# LEDARRAYHI.net
KiCad netlist of a schematic drawn in EAGLE
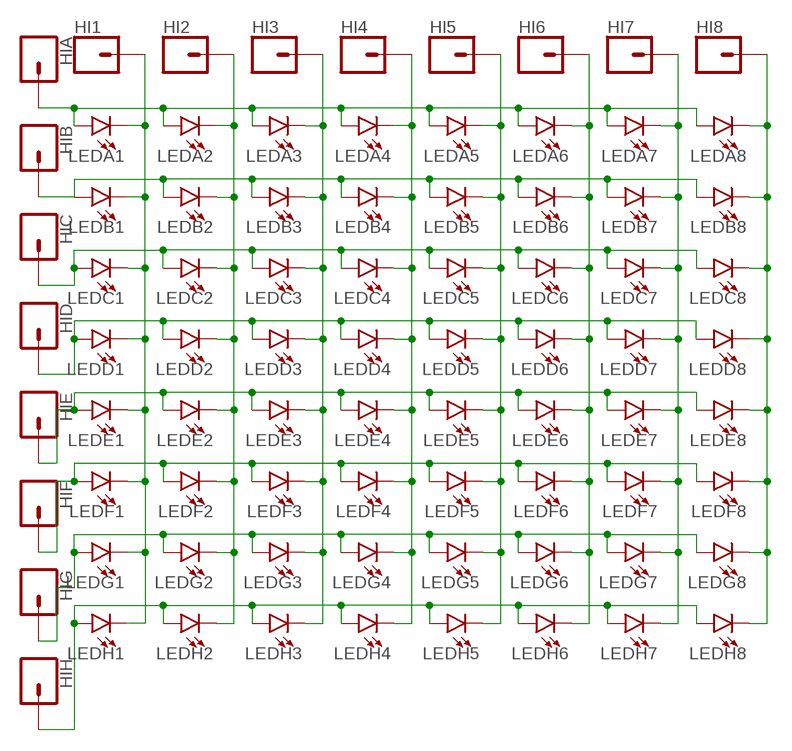
[diagram p0: schematic, sheet 1]

(export (version "E")
  (design (tool "Eeschema 10.0.6"))
  (components
    (comp (ref "HI1")
      (value "CONN_01PTH_NO_SILK_KIT")
      (footprint "eagle-import:1X01NS_KIT")
      (libsource (lib "eagle-import") (part "CONN_01PTH_NO_SILK_KIT"))
    )
    (comp (ref "HI2")
      (value "CONN_01PTH_NO_SILK_KIT")
      (footprint "eagle-import:1X01NS_KIT")
      (libsource (lib "eagle-import") (part "CONN_01PTH_NO_SILK_KIT"))
    )
    (comp (ref "HI3")
      (value "CONN_01PTH_NO_SILK_KIT")
      (footprint "eagle-import:1X01NS_KIT")
      (libsource (lib "eagle-import") (part "CONN_01PTH_NO_SILK_KIT"))
    )
    (comp (ref "HI4")
      (value "CONN_01PTH_NO_SILK_KIT")
      (footprint "eagle-import:1X01NS_KIT")
      (libsource (lib "eagle-import") (part "CONN_01PTH_NO_SILK_KIT"))
    )
    (comp (ref "HI5")
      (value "CONN_01PTH_NO_SILK_KIT")
      (footprint "eagle-import:1X01NS_KIT")
      (libsource (lib "eagle-import") (part "CONN_01PTH_NO_SILK_KIT"))
    )
    (comp (ref "HI6")
      (value "CONN_01PTH_NO_SILK_KIT")
      (footprint "eagle-import:1X01NS_KIT")
      (libsource (lib "eagle-import") (part "CONN_01PTH_NO_SILK_KIT"))
    )
    (comp (ref "HI7")
      (value "CONN_01PTH_NO_SILK_KIT")
      (footprint "eagle-import:1X01NS_KIT")
      (libsource (lib "eagle-import") (part "CONN_01PTH_NO_SILK_KIT"))
    )
    (comp (ref "HI8")
      (value "CONN_01PTH_NO_SILK_KIT")
      (footprint "eagle-import:1X01NS_KIT")
      (libsource (lib "eagle-import") (part "CONN_01PTH_NO_SILK_KIT"))
    )
    (comp (ref "HIA")
      (value "CONN_01PTH_NO_SILK_KIT")
      (footprint "eagle-import:1X01NS_KIT")
      (libsource (lib "eagle-import") (part "CONN_01PTH_NO_SILK_KIT"))
    )
    (comp (ref "HIB")
      (value "CONN_01PTH_NO_SILK_KIT")
      (footprint "eagle-import:1X01NS_KIT")
      (libsource (lib "eagle-import") (part "CONN_01PTH_NO_SILK_KIT"))
    )
    (comp (ref "HIC")
      (value "CONN_01PTH_NO_SILK_KIT")
      (footprint "eagle-import:1X01NS_KIT")
      (libsource (lib "eagle-import") (part "CONN_01PTH_NO_SILK_KIT"))
    )
    (comp (ref "HID")
      (value "CONN_01PTH_NO_SILK_KIT")
      (footprint "eagle-import:1X01NS_KIT")
      (libsource (lib "eagle-import") (part "CONN_01PTH_NO_SILK_KIT"))
    )
    (comp (ref "HIE")
      (value "CONN_01PTH_NO_SILK_KIT")
      (footprint "eagle-import:1X01NS_KIT")
      (libsource (lib "eagle-import") (part "CONN_01PTH_NO_SILK_KIT"))
    )
    (comp (ref "HIF")
      (value "CONN_01PTH_NO_SILK_KIT")
      (footprint "eagle-import:1X01NS_KIT")
      (libsource (lib "eagle-import") (part "CONN_01PTH_NO_SILK_KIT"))
    )
    (comp (ref "HIG")
      (value "CONN_01PTH_NO_SILK_KIT")
      (footprint "eagle-import:1X01NS_KIT")
      (libsource (lib "eagle-import") (part "CONN_01PTH_NO_SILK_KIT"))
    )
    (comp (ref "HIH")
      (value "CONN_01PTH_NO_SILK_KIT")
      (footprint "eagle-import:1X01NS_KIT")
      (libsource (lib "eagle-import") (part "CONN_01PTH_NO_SILK_KIT"))
    )
    (comp (ref "LEDA1")
      (value "LED3MM")
      (footprint "eagle-import:LED_3MM")
      (libsource (lib "eagle-import") (part "LED3MM"))
    )
    (comp (ref "LEDA2")
      (value "LED3MM")
      (footprint "eagle-import:LED_3MM")
      (libsource (lib "eagle-import") (part "LED3MM"))
    )
    (comp (ref "LEDA3")
      (value "LED3MM")
      (footprint "eagle-import:LED_3MM")
      (libsource (lib "eagle-import") (part "LED3MM"))
    )
    (comp (ref "LEDA4")
      (value "LED3MM")
      (footprint "eagle-import:LED_3MM")
      (libsource (lib "eagle-import") (part "LED3MM"))
    )
    (comp (ref "LEDA5")
      (value "LED3MM")
      (footprint "eagle-import:LED_3MM")
      (libsource (lib "eagle-import") (part "LED3MM"))
    )
    (comp (ref "LEDA6")
      (value "LED3MM")
      (footprint "eagle-import:LED_3MM")
      (libsource (lib "eagle-import") (part "LED3MM"))
    )
    (comp (ref "LEDA7")
      (value "LED3MM")
      (footprint "eagle-import:LED_3MM")
      (libsource (lib "eagle-import") (part "LED3MM"))
    )
    (comp (ref "LEDA8")
      (value "LED3MM")
      (footprint "eagle-import:LED_3MM")
      (libsource (lib "eagle-import") (part "LED3MM"))
    )
    (comp (ref "LEDB1")
      (value "LED3MM")
      (footprint "eagle-import:LED_3MM")
      (libsource (lib "eagle-import") (part "LED3MM"))
    )
    (comp (ref "LEDB2")
      (value "LED3MM")
      (footprint "eagle-import:LED_3MM")
      (libsource (lib "eagle-import") (part "LED3MM"))
    )
    (comp (ref "LEDB3")
      (value "LED3MM")
      (footprint "eagle-import:LED_3MM")
      (libsource (lib "eagle-import") (part "LED3MM"))
    )
    (comp (ref "LEDB4")
      (value "LED3MM")
      (footprint "eagle-import:LED_3MM")
      (libsource (lib "eagle-import") (part "LED3MM"))
    )
    (comp (ref "LEDB5")
      (value "LED3MM")
      (footprint "eagle-import:LED_3MM")
      (libsource (lib "eagle-import") (part "LED3MM"))
    )
    (comp (ref "LEDB6")
      (value "LED3MM")
      (footprint "eagle-import:LED_3MM")
      (libsource (lib "eagle-import") (part "LED3MM"))
    )
    (comp (ref "LEDB7")
      (value "LED3MM")
      (footprint "eagle-import:LED_3MM")
      (libsource (lib "eagle-import") (part "LED3MM"))
    )
    (comp (ref "LEDB8")
      (value "LED3MM")
      (footprint "eagle-import:LED_3MM")
      (libsource (lib "eagle-import") (part "LED3MM"))
    )
    (comp (ref "LEDC1")
      (value "LED3MM")
      (footprint "eagle-import:LED_3MM")
      (libsource (lib "eagle-import") (part "LED3MM"))
    )
    (comp (ref "LEDC2")
      (value "LED3MM")
      (footprint "eagle-import:LED_3MM")
      (libsource (lib "eagle-import") (part "LED3MM"))
    )
    (comp (ref "LEDC3")
      (value "LED3MM")
      (footprint "eagle-import:LED_3MM")
      (libsource (lib "eagle-import") (part "LED3MM"))
    )
    (comp (ref "LEDC4")
      (value "LED3MM")
      (footprint "eagle-import:LED_3MM")
      (libsource (lib "eagle-import") (part "LED3MM"))
    )
    (comp (ref "LEDC5")
      (value "LED3MM")
      (footprint "eagle-import:LED_3MM")
      (libsource (lib "eagle-import") (part "LED3MM"))
    )
    (comp (ref "LEDC6")
      (value "LED3MM")
      (footprint "eagle-import:LED_3MM")
      (libsource (lib "eagle-import") (part "LED3MM"))
    )
    (comp (ref "LEDC7")
      (value "LED3MM")
      (footprint "eagle-import:LED_3MM")
      (libsource (lib "eagle-import") (part "LED3MM"))
    )
    (comp (ref "LEDC8")
      (value "LED3MM")
      (footprint "eagle-import:LED_3MM")
      (libsource (lib "eagle-import") (part "LED3MM"))
    )
    (comp (ref "LEDD1")
      (value "LED3MM")
      (footprint "eagle-import:LED_3MM")
      (libsource (lib "eagle-import") (part "LED3MM"))
    )
    (comp (ref "LEDD2")
      (value "LED3MM")
      (footprint "eagle-import:LED_3MM")
      (libsource (lib "eagle-import") (part "LED3MM"))
    )
    (comp (ref "LEDD3")
      (value "LED3MM")
      (footprint "eagle-import:LED_3MM")
      (libsource (lib "eagle-import") (part "LED3MM"))
    )
    (comp (ref "LEDD4")
      (value "LED3MM")
      (footprint "eagle-import:LED_3MM")
      (libsource (lib "eagle-import") (part "LED3MM"))
    )
    (comp (ref "LEDD5")
      (value "LED3MM")
      (footprint "eagle-import:LED_3MM")
      (libsource (lib "eagle-import") (part "LED3MM"))
    )
    (comp (ref "LEDD6")
      (value "LED3MM")
      (footprint "eagle-import:LED_3MM")
      (libsource (lib "eagle-import") (part "LED3MM"))
    )
    (comp (ref "LEDD7")
      (value "LED3MM")
      (footprint "eagle-import:LED_3MM")
      (libsource (lib "eagle-import") (part "LED3MM"))
    )
    (comp (ref "LEDD8")
      (value "LED3MM")
      (footprint "eagle-import:LED_3MM")
      (libsource (lib "eagle-import") (part "LED3MM"))
    )
    (comp (ref "LEDE1")
      (value "LED3MM")
      (footprint "eagle-import:LED_3MM")
      (libsource (lib "eagle-import") (part "LED3MM"))
    )
    (comp (ref "LEDE2")
      (value "LED3MM")
      (footprint "eagle-import:LED_3MM")
      (libsource (lib "eagle-import") (part "LED3MM"))
    )
    (comp (ref "LEDE3")
      (value "LED3MM")
      (footprint "eagle-import:LED_3MM")
      (libsource (lib "eagle-import") (part "LED3MM"))
    )
    (comp (ref "LEDE4")
      (value "LED3MM")
      (footprint "eagle-import:LED_3MM")
      (libsource (lib "eagle-import") (part "LED3MM"))
    )
    (comp (ref "LEDE5")
      (value "LED3MM")
      (footprint "eagle-import:LED_3MM")
      (libsource (lib "eagle-import") (part "LED3MM"))
    )
    (comp (ref "LEDE6")
      (value "LED3MM")
      (footprint "eagle-import:LED_3MM")
      (libsource (lib "eagle-import") (part "LED3MM"))
    )
    (comp (ref "LEDE7")
      (value "LED3MM")
      (footprint "eagle-import:LED_3MM")
      (libsource (lib "eagle-import") (part "LED3MM"))
    )
    (comp (ref "LEDE8")
      (value "LED3MM")
      (footprint "eagle-import:LED_3MM")
      (libsource (lib "eagle-import") (part "LED3MM"))
    )
    (comp (ref "LEDF1")
      (value "LED3MM")
      (footprint "eagle-import:LED_3MM")
      (libsource (lib "eagle-import") (part "LED3MM"))
    )
    (comp (ref "LEDF2")
      (value "LED3MM")
      (footprint "eagle-import:LED_3MM")
      (libsource (lib "eagle-import") (part "LED3MM"))
    )
    (comp (ref "LEDF3")
      (value "LED3MM")
      (footprint "eagle-import:LED_3MM")
      (libsource (lib "eagle-import") (part "LED3MM"))
    )
    (comp (ref "LEDF4")
      (value "LED3MM")
      (footprint "eagle-import:LED_3MM")
      (libsource (lib "eagle-import") (part "LED3MM"))
    )
    (comp (ref "LEDF5")
      (value "LED3MM")
      (footprint "eagle-import:LED_3MM")
      (libsource (lib "eagle-import") (part "LED3MM"))
    )
    (comp (ref "LEDF6")
      (value "LED3MM")
      (footprint "eagle-import:LED_3MM")
      (libsource (lib "eagle-import") (part "LED3MM"))
    )
    (comp (ref "LEDF7")
      (value "LED3MM")
      (footprint "eagle-import:LED_3MM")
      (libsource (lib "eagle-import") (part "LED3MM"))
    )
    (comp (ref "LEDF8")
      (value "LED3MM")
      (footprint "eagle-import:LED_3MM")
      (libsource (lib "eagle-import") (part "LED3MM"))
    )
    (comp (ref "LEDG1")
      (value "LED3MM")
      (footprint "eagle-import:LED_3MM")
      (libsource (lib "eagle-import") (part "LED3MM"))
    )
    (comp (ref "LEDG2")
      (value "LED3MM")
      (footprint "eagle-import:LED_3MM")
      (libsource (lib "eagle-import") (part "LED3MM"))
    )
    (comp (ref "LEDG3")
      (value "LED3MM")
      (footprint "eagle-import:LED_3MM")
      (libsource (lib "eagle-import") (part "LED3MM"))
    )
    (comp (ref "LEDG4")
      (value "LED3MM")
      (footprint "eagle-import:LED_3MM")
      (libsource (lib "eagle-import") (part "LED3MM"))
    )
    (comp (ref "LEDG5")
      (value "LED3MM")
      (footprint "eagle-import:LED_3MM")
      (libsource (lib "eagle-import") (part "LED3MM"))
    )
    (comp (ref "LEDG6")
      (value "LED3MM")
      (footprint "eagle-import:LED_3MM")
      (libsource (lib "eagle-import") (part "LED3MM"))
    )
    (comp (ref "LEDG7")
      (value "LED3MM")
      (footprint "eagle-import:LED_3MM")
      (libsource (lib "eagle-import") (part "LED3MM"))
    )
    (comp (ref "LEDG8")
      (value "LED3MM")
      (footprint "eagle-import:LED_3MM")
      (libsource (lib "eagle-import") (part "LED3MM"))
    )
    (comp (ref "LEDH1")
      (value "LED3MM")
      (footprint "eagle-import:LED_3MM")
      (libsource (lib "eagle-import") (part "LED3MM"))
    )
    (comp (ref "LEDH2")
      (value "LED3MM")
      (footprint "eagle-import:LED_3MM")
      (libsource (lib "eagle-import") (part "LED3MM"))
    )
    (comp (ref "LEDH3")
      (value "LED3MM")
      (footprint "eagle-import:LED_3MM")
      (libsource (lib "eagle-import") (part "LED3MM"))
    )
    (comp (ref "LEDH4")
      (value "LED3MM")
      (footprint "eagle-import:LED_3MM")
      (libsource (lib "eagle-import") (part "LED3MM"))
    )
    (comp (ref "LEDH5")
      (value "LED3MM")
      (footprint "eagle-import:LED_3MM")
      (libsource (lib "eagle-import") (part "LED3MM"))
    )
    (comp (ref "LEDH6")
      (value "LED3MM")
      (footprint "eagle-import:LED_3MM")
      (libsource (lib "eagle-import") (part "LED3MM"))
    )
    (comp (ref "LEDH7")
      (value "LED3MM")
      (footprint "eagle-import:LED_3MM")
      (libsource (lib "eagle-import") (part "LED3MM"))
    )
    (comp (ref "LEDH8")
      (value "LED3MM")
      (footprint "eagle-import:LED_3MM")
      (libsource (lib "eagle-import") (part "LED3MM"))
    )
  )
  (nets
    (net (code "1") (name "Net-(HIA-Pad1)") (class "Default")
      (node (ref "HIA") (pin "1") (pinfunction "1_1") (pintype "passive"))
      (node (ref "LEDA1") (pin "A") (pinfunction "A_A") (pintype "passive"))
      (node (ref "LEDA2") (pin "A") (pinfunction "A_A") (pintype "passive"))
      (node (ref "LEDA3") (pin "A") (pinfunction "A_A") (pintype "passive"))
      (node (ref "LEDA4") (pin "A") (pinfunction "A_A") (pintype "passive"))
      (node (ref "LEDA5") (pin "A") (pinfunction "A_A") (pintype "passive"))
      (node (ref "LEDA6") (pin "A") (pinfunction "A_A") (pintype "passive"))
      (node (ref "LEDA7") (pin "A") (pinfunction "A_A") (pintype "passive"))
      (node (ref "LEDA8") (pin "A") (pinfunction "A_A") (pintype "passive"))
    )
    (net (code "2") (name "Net-(HIB-Pad1)") (class "Default")
      (node (ref "HIB") (pin "1") (pinfunction "1_1") (pintype "passive"))
      (node (ref "LEDB1") (pin "A") (pinfunction "A_A") (pintype "passive"))
      (node (ref "LEDB2") (pin "A") (pinfunction "A_A") (pintype "passive"))
      (node (ref "LEDB3") (pin "A") (pinfunction "A_A") (pintype "passive"))
      (node (ref "LEDB4") (pin "A") (pinfunction "A_A") (pintype "passive"))
      (node (ref "LEDB5") (pin "A") (pinfunction "A_A") (pintype "passive"))
      (node (ref "LEDB6") (pin "A") (pinfunction "A_A") (pintype "passive"))
      (node (ref "LEDB7") (pin "A") (pinfunction "A_A") (pintype "passive"))
      (node (ref "LEDB8") (pin "A") (pinfunction "A_A") (pintype "passive"))
    )
    (net (code "3") (name "Net-(HIC-Pad1)") (class "Default")
      (node (ref "HIC") (pin "1") (pinfunction "1_1") (pintype "passive"))
      (node (ref "LEDC1") (pin "A") (pinfunction "A_A") (pintype "passive"))
      (node (ref "LEDC2") (pin "A") (pinfunction "A_A") (pintype "passive"))
      (node (ref "LEDC3") (pin "A") (pinfunction "A_A") (pintype "passive"))
      (node (ref "LEDC4") (pin "A") (pinfunction "A_A") (pintype "passive"))
      (node (ref "LEDC5") (pin "A") (pinfunction "A_A") (pintype "passive"))
      (node (ref "LEDC6") (pin "A") (pinfunction "A_A") (pintype "passive"))
      (node (ref "LEDC7") (pin "A") (pinfunction "A_A") (pintype "passive"))
      (node (ref "LEDC8") (pin "A") (pinfunction "A_A") (pintype "passive"))
    )
    (net (code "4") (name "Net-(HID-Pad1)") (class "Default")
      (node (ref "HID") (pin "1") (pinfunction "1_1") (pintype "passive"))
      (node (ref "LEDD1") (pin "A") (pinfunction "A_A") (pintype "passive"))
      (node (ref "LEDD2") (pin "A") (pinfunction "A_A") (pintype "passive"))
      (node (ref "LEDD3") (pin "A") (pinfunction "A_A") (pintype "passive"))
      (node (ref "LEDD4") (pin "A") (pinfunction "A_A") (pintype "passive"))
      (node (ref "LEDD5") (pin "A") (pinfunction "A_A") (pintype "passive"))
      (node (ref "LEDD6") (pin "A") (pinfunction "A_A") (pintype "passive"))
      (node (ref "LEDD7") (pin "A") (pinfunction "A_A") (pintype "passive"))
      (node (ref "LEDD8") (pin "A") (pinfunction "A_A") (pintype "passive"))
    )
    (net (code "5") (name "Net-(HIE-Pad1)") (class "Default")
      (node (ref "HIE") (pin "1") (pinfunction "1_1") (pintype "passive"))
      (node (ref "LEDE1") (pin "A") (pinfunction "A_A") (pintype "passive"))
      (node (ref "LEDE2") (pin "A") (pinfunction "A_A") (pintype "passive"))
      (node (ref "LEDE3") (pin "A") (pinfunction "A_A") (pintype "passive"))
      (node (ref "LEDE4") (pin "A") (pinfunction "A_A") (pintype "passive"))
      (node (ref "LEDE5") (pin "A") (pinfunction "A_A") (pintype "passive"))
      (node (ref "LEDE6") (pin "A") (pinfunction "A_A") (pintype "passive"))
      (node (ref "LEDE7") (pin "A") (pinfunction "A_A") (pintype "passive"))
      (node (ref "LEDE8") (pin "A") (pinfunction "A_A") (pintype "passive"))
    )
    (net (code "6") (name "Net-(HIF-Pad1)") (class "Default")
      (node (ref "HIF") (pin "1") (pinfunction "1_1") (pintype "passive"))
      (node (ref "LEDF1") (pin "A") (pinfunction "A_A") (pintype "passive"))
      (node (ref "LEDF2") (pin "A") (pinfunction "A_A") (pintype "passive"))
      (node (ref "LEDF3") (pin "A") (pinfunction "A_A") (pintype "passive"))
      (node (ref "LEDF4") (pin "A") (pinfunction "A_A") (pintype "passive"))
      (node (ref "LEDF5") (pin "A") (pinfunction "A_A") (pintype "passive"))
      (node (ref "LEDF6") (pin "A") (pinfunction "A_A") (pintype "passive"))
      (node (ref "LEDF7") (pin "A") (pinfunction "A_A") (pintype "passive"))
      (node (ref "LEDF8") (pin "A") (pinfunction "A_A") (pintype "passive"))
    )
    (net (code "7") (name "Net-(HIG-Pad1)") (class "Default")
      (node (ref "HIG") (pin "1") (pinfunction "1_1") (pintype "passive"))
      (node (ref "LEDG1") (pin "A") (pinfunction "A_A") (pintype "passive"))
      (node (ref "LEDG2") (pin "A") (pinfunction "A_A") (pintype "passive"))
      (node (ref "LEDG3") (pin "A") (pinfunction "A_A") (pintype "passive"))
      (node (ref "LEDG4") (pin "A") (pinfunction "A_A") (pintype "passive"))
      (node (ref "LEDG5") (pin "A") (pinfunction "A_A") (pintype "passive"))
      (node (ref "LEDG6") (pin "A") (pinfunction "A_A") (pintype "passive"))
      (node (ref "LEDG7") (pin "A") (pinfunction "A_A") (pintype "passive"))
      (node (ref "LEDG8") (pin "A") (pinfunction "A_A") (pintype "passive"))
    )
    (net (code "8") (name "Net-(HIH-Pad1)") (class "Default")
      (node (ref "HIH") (pin "1") (pinfunction "1_1") (pintype "passive"))
      (node (ref "LEDH1") (pin "A") (pinfunction "A_A") (pintype "passive"))
      (node (ref "LEDH2") (pin "A") (pinfunction "A_A") (pintype "passive"))
      (node (ref "LEDH3") (pin "A") (pinfunction "A_A") (pintype "passive"))
      (node (ref "LEDH4") (pin "A") (pinfunction "A_A") (pintype "passive"))
      (node (ref "LEDH5") (pin "A") (pinfunction "A_A") (pintype "passive"))
      (node (ref "LEDH6") (pin "A") (pinfunction "A_A") (pintype "passive"))
      (node (ref "LEDH7") (pin "A") (pinfunction "A_A") (pintype "passive"))
      (node (ref "LEDH8") (pin "A") (pinfunction "A_A") (pintype "passive"))
    )
    (net (code "9") (name "Net-(LEDA1-C)") (class "Default")
      (node (ref "HI1") (pin "1") (pinfunction "1_1") (pintype "passive"))
      (node (ref "LEDA1") (pin "K") (pinfunction "C_K") (pintype "passive"))
      (node (ref "LEDB1") (pin "K") (pinfunction "C_K") (pintype "passive"))
      (node (ref "LEDC1") (pin "K") (pinfunction "C_K") (pintype "passive"))
      (node (ref "LEDD1") (pin "K") (pinfunction "C_K") (pintype "passive"))
      (node (ref "LEDE1") (pin "K") (pinfunction "C_K") (pintype "passive"))
      (node (ref "LEDF1") (pin "K") (pinfunction "C_K") (pintype "passive"))
      (node (ref "LEDG1") (pin "K") (pinfunction "C_K") (pintype "passive"))
      (node (ref "LEDH1") (pin "K") (pinfunction "C_K") (pintype "passive"))
    )
    (net (code "10") (name "Net-(LEDA2-C)") (class "Default")
      (node (ref "HI2") (pin "1") (pinfunction "1_1") (pintype "passive"))
      (node (ref "LEDA2") (pin "K") (pinfunction "C_K") (pintype "passive"))
      (node (ref "LEDB2") (pin "K") (pinfunction "C_K") (pintype "passive"))
      (node (ref "LEDC2") (pin "K") (pinfunction "C_K") (pintype "passive"))
      (node (ref "LEDD2") (pin "K") (pinfunction "C_K") (pintype "passive"))
      (node (ref "LEDE2") (pin "K") (pinfunction "C_K") (pintype "passive"))
      (node (ref "LEDF2") (pin "K") (pinfunction "C_K") (pintype "passive"))
      (node (ref "LEDG2") (pin "K") (pinfunction "C_K") (pintype "passive"))
      (node (ref "LEDH2") (pin "K") (pinfunction "C_K") (pintype "passive"))
    )
    (net (code "11") (name "Net-(LEDA3-C)") (class "Default")
      (node (ref "HI3") (pin "1") (pinfunction "1_1") (pintype "passive"))
      (node (ref "LEDA3") (pin "K") (pinfunction "C_K") (pintype "passive"))
      (node (ref "LEDB3") (pin "K") (pinfunction "C_K") (pintype "passive"))
      (node (ref "LEDC3") (pin "K") (pinfunction "C_K") (pintype "passive"))
      (node (ref "LEDD3") (pin "K") (pinfunction "C_K") (pintype "passive"))
      (node (ref "LEDE3") (pin "K") (pinfunction "C_K") (pintype "passive"))
      (node (ref "LEDF3") (pin "K") (pinfunction "C_K") (pintype "passive"))
      (node (ref "LEDG3") (pin "K") (pinfunction "C_K") (pintype "passive"))
      (node (ref "LEDH3") (pin "K") (pinfunction "C_K") (pintype "passive"))
    )
    (net (code "12") (name "Net-(LEDA4-C)") (class "Default")
      (node (ref "HI4") (pin "1") (pinfunction "1_1") (pintype "passive"))
      (node (ref "LEDA4") (pin "K") (pinfunction "C_K") (pintype "passive"))
      (node (ref "LEDB4") (pin "K") (pinfunction "C_K") (pintype "passive"))
      (node (ref "LEDC4") (pin "K") (pinfunction "C_K") (pintype "passive"))
      (node (ref "LEDD4") (pin "K") (pinfunction "C_K") (pintype "passive"))
      (node (ref "LEDE4") (pin "K") (pinfunction "C_K") (pintype "passive"))
      (node (ref "LEDF4") (pin "K") (pinfunction "C_K") (pintype "passive"))
      (node (ref "LEDG4") (pin "K") (pinfunction "C_K") (pintype "passive"))
      (node (ref "LEDH4") (pin "K") (pinfunction "C_K") (pintype "passive"))
    )
    (net (code "13") (name "Net-(LEDA5-C)") (class "Default")
      (node (ref "HI5") (pin "1") (pinfunction "1_1") (pintype "passive"))
      (node (ref "LEDA5") (pin "K") (pinfunction "C_K") (pintype "passive"))
      (node (ref "LEDB5") (pin "K") (pinfunction "C_K") (pintype "passive"))
      (node (ref "LEDC5") (pin "K") (pinfunction "C_K") (pintype "passive"))
      (node (ref "LEDD5") (pin "K") (pinfunction "C_K") (pintype "passive"))
      (node (ref "LEDE5") (pin "K") (pinfunction "C_K") (pintype "passive"))
      (node (ref "LEDF5") (pin "K") (pinfunction "C_K") (pintype "passive"))
      (node (ref "LEDG5") (pin "K") (pinfunction "C_K") (pintype "passive"))
      (node (ref "LEDH5") (pin "K") (pinfunction "C_K") (pintype "passive"))
    )
    (net (code "14") (name "Net-(LEDA6-C)") (class "Default")
      (node (ref "HI6") (pin "1") (pinfunction "1_1") (pintype "passive"))
      (node (ref "LEDA6") (pin "K") (pinfunction "C_K") (pintype "passive"))
      (node (ref "LEDB6") (pin "K") (pinfunction "C_K") (pintype "passive"))
      (node (ref "LEDC6") (pin "K") (pinfunction "C_K") (pintype "passive"))
      (node (ref "LEDD6") (pin "K") (pinfunction "C_K") (pintype "passive"))
      (node (ref "LEDE6") (pin "K") (pinfunction "C_K") (pintype "passive"))
      (node (ref "LEDF6") (pin "K") (pinfunction "C_K") (pintype "passive"))
      (node (ref "LEDG6") (pin "K") (pinfunction "C_K") (pintype "passive"))
      (node (ref "LEDH6") (pin "K") (pinfunction "C_K") (pintype "passive"))
    )
    (net (code "15") (name "Net-(LEDA7-C)") (class "Default")
      (node (ref "HI7") (pin "1") (pinfunction "1_1") (pintype "passive"))
      (node (ref "LEDA7") (pin "K") (pinfunction "C_K") (pintype "passive"))
      (node (ref "LEDB7") (pin "K") (pinfunction "C_K") (pintype "passive"))
      (node (ref "LEDC7") (pin "K") (pinfunction "C_K") (pintype "passive"))
      (node (ref "LEDD7") (pin "K") (pinfunction "C_K") (pintype "passive"))
      (node (ref "LEDE7") (pin "K") (pinfunction "C_K") (pintype "passive"))
      (node (ref "LEDF7") (pin "K") (pinfunction "C_K") (pintype "passive"))
      (node (ref "LEDG7") (pin "K") (pinfunction "C_K") (pintype "passive"))
      (node (ref "LEDH7") (pin "K") (pinfunction "C_K") (pintype "passive"))
    )
    (net (code "16") (name "Net-(LEDA8-C)") (class "Default")
      (node (ref "HI8") (pin "1") (pinfunction "1_1") (pintype "passive"))
      (node (ref "LEDA8") (pin "K") (pinfunction "C_K") (pintype "passive"))
      (node (ref "LEDB8") (pin "K") (pinfunction "C_K") (pintype "passive"))
      (node (ref "LEDC8") (pin "K") (pinfunction "C_K") (pintype "passive"))
      (node (ref "LEDD8") (pin "K") (pinfunction "C_K") (pintype "passive"))
      (node (ref "LEDE8") (pin "K") (pinfunction "C_K") (pintype "passive"))
      (node (ref "LEDF8") (pin "K") (pinfunction "C_K") (pintype "passive"))
      (node (ref "LEDG8") (pin "K") (pinfunction "C_K") (pintype "passive"))
      (node (ref "LEDH8") (pin "K") (pinfunction "C_K") (pintype "passive"))
    )
  )
)
